# final_design.net
KiCad netlist of a schematic drawn in Altium Designer
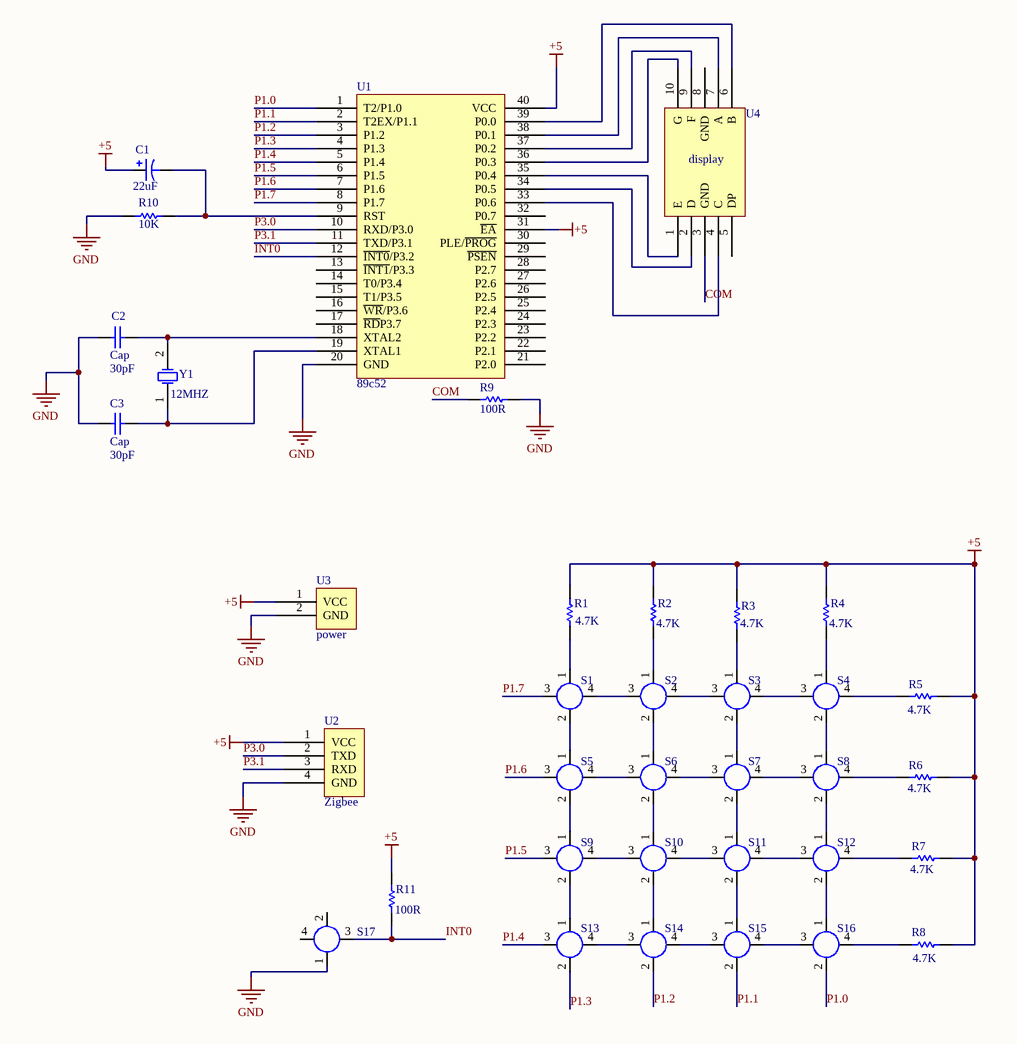
[diagram p0: final_design.SchDoc]

(export (version "E")
  (design (tool "Eeschema 10.0.6"))
  (components
    (comp (ref "C1")
      (value "22uF")
      (footprint "RB")
      (description "Polarized Capacitor (Radial)")
      (fields (field (name "Comment") "Cap Pol1") (field (name "PUBLISHER") "Altium Limited"))
      (libsource (lib "Miscellaneous Devices") (part "Cap Pol1"))
    )
    (comp (ref "C2")
      (value "Cap")
      (footprint "MLCC")
      (description "Capacitor")
      (fields (field (name "ALTIUM_VALUE") "30pF") (field (name "PUBLISHER") "Altium Limited"))
      (libsource (lib "Miscellaneous Devices") (part "Cap"))
    )
    (comp (ref "C3")
      (value "Cap")
      (footprint "MLCC")
      (description "Capacitor")
      (fields (field (name "ALTIUM_VALUE") "30pF") (field (name "PUBLISHER") "Altium Limited"))
      (libsource (lib "Miscellaneous Devices") (part "Cap"))
    )
    (comp (ref "R1")
      (value "4.7K")
      (footprint "Ris")
      (description "Resistor")
      (fields (field (name "Comment") "Res1") (field (name "PUBLISHER") "Altium Limited"))
      (libsource (lib "Miscellaneous Devices") (part "Res1"))
    )
    (comp (ref "R2")
      (value "4.7K")
      (footprint "Ris")
      (description "Resistor")
      (fields (field (name "Comment") "Res1") (field (name "PUBLISHER") "Altium Limited"))
      (libsource (lib "Miscellaneous Devices") (part "Res1"))
    )
    (comp (ref "R3")
      (value "4.7K")
      (footprint "Ris")
      (description "Resistor")
      (fields (field (name "Comment") "Res1") (field (name "PUBLISHER") "Altium Limited"))
      (libsource (lib "Miscellaneous Devices") (part "Res1"))
    )
    (comp (ref "R4")
      (value "4.7K")
      (footprint "Ris")
      (description "Resistor")
      (fields (field (name "Comment") "Res1") (field (name "PUBLISHER") "Altium Limited"))
      (libsource (lib "Miscellaneous Devices") (part "Res1"))
    )
    (comp (ref "R5")
      (value "4.7K")
      (footprint "Ris")
      (description "Resistor")
      (fields (field (name "Comment") "Res1") (field (name "PUBLISHER") "Altium Limited"))
      (libsource (lib "Miscellaneous Devices") (part "Res1"))
    )
    (comp (ref "R6")
      (value "4.7K")
      (footprint "Ris")
      (description "Resistor")
      (fields (field (name "Comment") "Res1") (field (name "PUBLISHER") "Altium Limited"))
      (libsource (lib "Miscellaneous Devices") (part "Res1"))
    )
    (comp (ref "R7")
      (value "4.7K")
      (footprint "Ris")
      (description "Resistor")
      (fields (field (name "Comment") "Res1") (field (name "PUBLISHER") "Altium Limited"))
      (libsource (lib "Miscellaneous Devices") (part "Res1"))
    )
    (comp (ref "R8")
      (value "4.7K")
      (footprint "Ris")
      (description "Resistor")
      (fields (field (name "Comment") "Res1") (field (name "PUBLISHER") "Altium Limited"))
      (libsource (lib "Miscellaneous Devices") (part "Res1"))
    )
    (comp (ref "R9")
      (value "100R")
      (footprint "Ris")
      (description "Resistor")
      (fields (field (name "Comment") "Res1") (field (name "PUBLISHER") "Altium Limited"))
      (libsource (lib "Miscellaneous Devices") (part "Res1"))
    )
    (comp (ref "R10")
      (value "10K")
      (footprint "Ris")
      (description "Resistor")
      (fields (field (name "Comment") "Res1") (field (name "PUBLISHER") "Altium Limited"))
      (libsource (lib "Miscellaneous Devices") (part "Res1"))
    )
    (comp (ref "R11")
      (value "100R")
      (footprint "Ris")
      (description "Resistor")
      (fields (field (name "Comment") "Res1") (field (name "PUBLISHER") "Altium Limited"))
      (libsource (lib "Miscellaneous Devices") (part "Res1"))
    )
    (comp (ref "S1")
      (value "Button-4feet")
      (footprint "Button-4feet")
      (libsource (lib "final_design") (part "Button-4feet"))
    )
    (comp (ref "S2")
      (value "Button-4feet")
      (footprint "Button-4feet")
      (libsource (lib "final_design") (part "Button-4feet"))
    )
    (comp (ref "S3")
      (value "Button-4feet")
      (footprint "Button-4feet")
      (libsource (lib "final_design") (part "Button-4feet"))
    )
    (comp (ref "S4")
      (value "Button-4feet")
      (footprint "Button-4feet")
      (libsource (lib "final_design") (part "Button-4feet"))
    )
    (comp (ref "S5")
      (value "Button-4feet")
      (footprint "Button-4feet")
      (libsource (lib "final_design") (part "Button-4feet"))
    )
    (comp (ref "S6")
      (value "Button-4feet")
      (footprint "Button-4feet")
      (libsource (lib "final_design") (part "Button-4feet"))
    )
    (comp (ref "S7")
      (value "Button-4feet")
      (footprint "Button-4feet")
      (libsource (lib "final_design") (part "Button-4feet"))
    )
    (comp (ref "S8")
      (value "Button-4feet")
      (footprint "Button-4feet")
      (libsource (lib "final_design") (part "Button-4feet"))
    )
    (comp (ref "S9")
      (value "Button-4feet")
      (footprint "Button-4feet")
      (libsource (lib "final_design") (part "Button-4feet"))
    )
    (comp (ref "S10")
      (value "Button-4feet")
      (footprint "Button-4feet")
      (libsource (lib "final_design") (part "Button-4feet"))
    )
    (comp (ref "S11")
      (value "Button-4feet")
      (footprint "Button-4feet")
      (libsource (lib "final_design") (part "Button-4feet"))
    )
    (comp (ref "S12")
      (value "Button-4feet")
      (footprint "Button-4feet")
      (libsource (lib "final_design") (part "Button-4feet"))
    )
    (comp (ref "S13")
      (value "Button-4feet")
      (footprint "Button-4feet")
      (libsource (lib "final_design") (part "Button-4feet"))
    )
    (comp (ref "S14")
      (value "Button-4feet")
      (footprint "Button-4feet")
      (libsource (lib "final_design") (part "Button-4feet"))
    )
    (comp (ref "S15")
      (value "Button-4feet")
      (footprint "Button-4feet")
      (libsource (lib "final_design") (part "Button-4feet"))
    )
    (comp (ref "S16")
      (value "Button-4feet")
      (footprint "Button-4feet")
      (libsource (lib "final_design") (part "Button-4feet"))
    )
    (comp (ref "S17")
      (value "Button-4feet")
      (footprint "Button-4feet")
      (libsource (lib "final_design") (part "Button-4feet"))
    )
    (comp (ref "U1") (value "89c52") (footprint "89C52") (libsource (lib "final_design") (part "89c52")))
    (comp (ref "U2") (value "Zigbee") (footprint "Zigbee") (libsource (lib "final_design") (part "Zigbee")))
    (comp (ref "U3") (value "power") (footprint "Power") (libsource (lib "final_design") (part "power")))
    (comp (ref "U4") (value "display") (footprint "Dsplay") (libsource (lib "final_design") (part "display")))
    (comp (ref "Y1")
      (value "12MHZ")
      (footprint "Oscillator-11.0592MHZ")
      (description "Crystal Oscillator")
      (fields (field (name "PUBLISHER") "Altium Limited"))
      (libsource (lib "Miscellaneous Devices") (part "XTAL"))
    )
  )
  (nets
    (net (code "1") (name "+5") (class "Default")
      (node (ref "C1") (pin "1") (pinfunction "1_1") (pintype "passive"))
      (node (ref "R1") (pin "2") (pinfunction "2_2") (pintype "passive"))
      (node (ref "R11") (pin "2") (pinfunction "2_2") (pintype "passive"))
      (node (ref "R2") (pin "1") (pinfunction "1_1") (pintype "passive"))
      (node (ref "R3") (pin "2") (pinfunction "2_2") (pintype "passive"))
      (node (ref "R4") (pin "2") (pinfunction "2_2") (pintype "passive"))
      (node (ref "R5") (pin "1") (pinfunction "1_1") (pintype "passive"))
      (node (ref "R6") (pin "1") (pinfunction "1_1") (pintype "passive"))
      (node (ref "R7") (pin "1") (pinfunction "1_1") (pintype "passive"))
      (node (ref "R8") (pin "1") (pinfunction "1_1") (pintype "passive"))
      (node (ref "U1") (pin "31") (pinfunction "~{EA}_31") (pintype "passive"))
      (node (ref "U1") (pin "40") (pinfunction "VCC_40") (pintype "passive"))
      (node (ref "U2") (pin "1") (pinfunction "VCC_1") (pintype "passive"))
      (node (ref "U3") (pin "1") (pinfunction "VCC_1") (pintype "passive"))
    )
    (net (code "2") (name "/COM") (class "Default")
      (node (ref "R9") (pin "2") (pinfunction "2_2") (pintype "passive"))
      (node (ref "U4") (pin "3") (pinfunction "GND_3") (pintype "passive"))
    )
    (net (code "3") (name "/INT0") (class "Default")
      (node (ref "R11") (pin "1") (pinfunction "1_1") (pintype "passive"))
      (node (ref "S17") (pin "3") (pinfunction "3_3") (pintype "passive"))
      (node (ref "U1") (pin "12") (pinfunction "~{INT0}/P3.2_12") (pintype "passive"))
    )
    (net (code "4") (name "/P1.0") (class "Default")
      (node (ref "S16") (pin "2") (pinfunction "2_2") (pintype "passive"))
      (node (ref "U1") (pin "1") (pinfunction "T2/P1.0_1") (pintype "passive"))
    )
    (net (code "5") (name "/P1.1") (class "Default")
      (node (ref "S15") (pin "2") (pinfunction "2_2") (pintype "passive"))
      (node (ref "U1") (pin "2") (pinfunction "T2EX/P1.1_2") (pintype "passive"))
    )
    (net (code "6") (name "/P1.2") (class "Default")
      (node (ref "S14") (pin "2") (pinfunction "2_2") (pintype "passive"))
      (node (ref "U1") (pin "3") (pinfunction "P1.2_3") (pintype "passive"))
    )
    (net (code "7") (name "/P1.3") (class "Default")
      (node (ref "S13") (pin "2") (pinfunction "2_2") (pintype "passive"))
      (node (ref "U1") (pin "4") (pinfunction "P1.3_4") (pintype "passive"))
    )
    (net (code "8") (name "/P1.4") (class "Default")
      (node (ref "S13") (pin "3") (pinfunction "3_3") (pintype "passive"))
      (node (ref "U1") (pin "5") (pinfunction "P1.4_5") (pintype "passive"))
    )
    (net (code "9") (name "/P1.5") (class "Default")
      (node (ref "S9") (pin "3") (pinfunction "3_3") (pintype "passive"))
      (node (ref "U1") (pin "6") (pinfunction "P1.5_6") (pintype "passive"))
    )
    (net (code "10") (name "/P1.6") (class "Default")
      (node (ref "S5") (pin "3") (pinfunction "3_3") (pintype "passive"))
      (node (ref "U1") (pin "7") (pinfunction "P1.6_7") (pintype "passive"))
    )
    (net (code "11") (name "/P1.7") (class "Default")
      (node (ref "S1") (pin "3") (pinfunction "3_3") (pintype "passive"))
      (node (ref "U1") (pin "8") (pinfunction "P1.7_8") (pintype "passive"))
    )
    (net (code "12") (name "/P3.0") (class "Default")
      (node (ref "U1") (pin "10") (pinfunction "RXD/P3.0_10") (pintype "passive"))
      (node (ref "U2") (pin "2") (pinfunction "TXD_2") (pintype "passive"))
    )
    (net (code "13") (name "/P3.1") (class "Default")
      (node (ref "U1") (pin "11") (pinfunction "TXD/P3.1_11") (pintype "passive"))
      (node (ref "U2") (pin "3") (pinfunction "RXD_3") (pintype "passive"))
    )
    (net (code "14") (name "GND") (class "Default")
      (node (ref "C2") (pin "1") (pinfunction "1_1") (pintype "passive"))
      (node (ref "C3") (pin "1") (pinfunction "1_1") (pintype "passive"))
      (node (ref "R10") (pin "2") (pinfunction "2_2") (pintype "passive"))
      (node (ref "R9") (pin "1") (pinfunction "1_1") (pintype "passive"))
      (node (ref "S17") (pin "1") (pinfunction "41_1") (pintype "passive"))
      (node (ref "U1") (pin "20") (pinfunction "GND_20") (pintype "passive"))
      (node (ref "U2") (pin "4") (pinfunction "GND_4") (pintype "passive"))
      (node (ref "U3") (pin "2") (pinfunction "GND_2") (pintype "passive"))
    )
    (net (code "15") (name "Net-(R5-Pad2)") (class "Default")
      (node (ref "R5") (pin "2") (pinfunction "2_2") (pintype "passive"))
      (node (ref "S4") (pin "4") (pinfunction "4_4") (pintype "passive"))
    )
    (net (code "16") (name "Net-(R6-Pad2)") (class "Default")
      (node (ref "R6") (pin "2") (pinfunction "2_2") (pintype "passive"))
      (node (ref "S8") (pin "4") (pinfunction "4_4") (pintype "passive"))
    )
    (net (code "17") (name "Net-(R7-Pad2)") (class "Default")
      (node (ref "R7") (pin "2") (pinfunction "2_2") (pintype "passive"))
      (node (ref "S12") (pin "4") (pinfunction "4_4") (pintype "passive"))
    )
    (net (code "18") (name "Net-(R8-Pad2)") (class "Default")
      (node (ref "R8") (pin "2") (pinfunction "2_2") (pintype "passive"))
      (node (ref "S16") (pin "4") (pinfunction "4_4") (pintype "passive"))
    )
    (net (code "19") (name "Net-(S1-41)") (class "Default")
      (node (ref "R1") (pin "1") (pinfunction "1_1") (pintype "passive"))
      (node (ref "S1") (pin "1") (pinfunction "41_1") (pintype "passive"))
    )
    (net (code "20") (name "Net-(S1-Pad4)") (class "Default")
      (node (ref "S1") (pin "4") (pinfunction "4_4") (pintype "passive"))
      (node (ref "S2") (pin "3") (pinfunction "3_3") (pintype "passive"))
    )
    (net (code "21") (name "Net-(S2-41)") (class "Default")
      (node (ref "R2") (pin "2") (pinfunction "2_2") (pintype "passive"))
      (node (ref "S2") (pin "1") (pinfunction "41_1") (pintype "passive"))
    )
    (net (code "22") (name "Net-(S2-Pad4)") (class "Default")
      (node (ref "S2") (pin "4") (pinfunction "4_4") (pintype "passive"))
      (node (ref "S3") (pin "3") (pinfunction "3_3") (pintype "passive"))
    )
    (net (code "23") (name "Net-(S3-41)") (class "Default")
      (node (ref "R3") (pin "1") (pinfunction "1_1") (pintype "passive"))
      (node (ref "S3") (pin "1") (pinfunction "41_1") (pintype "passive"))
    )
    (net (code "24") (name "Net-(S3-Pad4)") (class "Default")
      (node (ref "S3") (pin "4") (pinfunction "4_4") (pintype "passive"))
      (node (ref "S4") (pin "3") (pinfunction "3_3") (pintype "passive"))
    )
    (net (code "25") (name "Net-(S4-41)") (class "Default")
      (node (ref "R4") (pin "1") (pinfunction "1_1") (pintype "passive"))
      (node (ref "S4") (pin "1") (pinfunction "41_1") (pintype "passive"))
    )
    (net (code "26") (name "Net-(S5-41)") (class "Default")
      (node (ref "S1") (pin "2") (pinfunction "2_2") (pintype "passive"))
      (node (ref "S5") (pin "1") (pinfunction "41_1") (pintype "passive"))
    )
    (net (code "27") (name "Net-(S5-Pad4)") (class "Default")
      (node (ref "S5") (pin "4") (pinfunction "4_4") (pintype "passive"))
      (node (ref "S6") (pin "3") (pinfunction "3_3") (pintype "passive"))
    )
    (net (code "28") (name "Net-(S6-41)") (class "Default")
      (node (ref "S2") (pin "2") (pinfunction "2_2") (pintype "passive"))
      (node (ref "S6") (pin "1") (pinfunction "41_1") (pintype "passive"))
    )
    (net (code "29") (name "Net-(S6-Pad4)") (class "Default")
      (node (ref "S6") (pin "4") (pinfunction "4_4") (pintype "passive"))
      (node (ref "S7") (pin "3") (pinfunction "3_3") (pintype "passive"))
    )
    (net (code "30") (name "Net-(S7-41)") (class "Default")
      (node (ref "S3") (pin "2") (pinfunction "2_2") (pintype "passive"))
      (node (ref "S7") (pin "1") (pinfunction "41_1") (pintype "passive"))
    )
    (net (code "31") (name "Net-(S7-Pad4)") (class "Default")
      (node (ref "S7") (pin "4") (pinfunction "4_4") (pintype "passive"))
      (node (ref "S8") (pin "3") (pinfunction "3_3") (pintype "passive"))
    )
    (net (code "32") (name "Net-(S8-41)") (class "Default")
      (node (ref "S4") (pin "2") (pinfunction "2_2") (pintype "passive"))
      (node (ref "S8") (pin "1") (pinfunction "41_1") (pintype "passive"))
    )
    (net (code "33") (name "Net-(S9-41)") (class "Default")
      (node (ref "S5") (pin "2") (pinfunction "2_2") (pintype "passive"))
      (node (ref "S9") (pin "1") (pinfunction "41_1") (pintype "passive"))
    )
    (net (code "34") (name "Net-(S10-41)") (class "Default")
      (node (ref "S10") (pin "1") (pinfunction "41_1") (pintype "passive"))
      (node (ref "S6") (pin "2") (pinfunction "2_2") (pintype "passive"))
    )
    (net (code "35") (name "Net-(S10-Pad3)") (class "Default")
      (node (ref "S10") (pin "3") (pinfunction "3_3") (pintype "passive"))
      (node (ref "S9") (pin "4") (pinfunction "4_4") (pintype "passive"))
    )
    (net (code "36") (name "Net-(S10-Pad4)") (class "Default")
      (node (ref "S10") (pin "4") (pinfunction "4_4") (pintype "passive"))
      (node (ref "S11") (pin "3") (pinfunction "3_3") (pintype "passive"))
    )
    (net (code "37") (name "Net-(S11-41)") (class "Default")
      (node (ref "S11") (pin "1") (pinfunction "41_1") (pintype "passive"))
      (node (ref "S7") (pin "2") (pinfunction "2_2") (pintype "passive"))
    )
    (net (code "38") (name "Net-(S11-Pad4)") (class "Default")
      (node (ref "S11") (pin "4") (pinfunction "4_4") (pintype "passive"))
      (node (ref "S12") (pin "3") (pinfunction "3_3") (pintype "passive"))
    )
    (net (code "39") (name "Net-(S12-41)") (class "Default")
      (node (ref "S12") (pin "1") (pinfunction "41_1") (pintype "passive"))
      (node (ref "S8") (pin "2") (pinfunction "2_2") (pintype "passive"))
    )
    (net (code "40") (name "Net-(S13-41)") (class "Default")
      (node (ref "S13") (pin "1") (pinfunction "41_1") (pintype "passive"))
      (node (ref "S9") (pin "2") (pinfunction "2_2") (pintype "passive"))
    )
    (net (code "41") (name "Net-(S13-Pad4)") (class "Default")
      (node (ref "S13") (pin "4") (pinfunction "4_4") (pintype "passive"))
      (node (ref "S14") (pin "3") (pinfunction "3_3") (pintype "passive"))
    )
    (net (code "42") (name "Net-(S14-41)") (class "Default")
      (node (ref "S10") (pin "2") (pinfunction "2_2") (pintype "passive"))
      (node (ref "S14") (pin "1") (pinfunction "41_1") (pintype "passive"))
    )
    (net (code "43") (name "Net-(S14-Pad4)") (class "Default")
      (node (ref "S14") (pin "4") (pinfunction "4_4") (pintype "passive"))
      (node (ref "S15") (pin "3") (pinfunction "3_3") (pintype "passive"))
    )
    (net (code "44") (name "Net-(S15-41)") (class "Default")
      (node (ref "S11") (pin "2") (pinfunction "2_2") (pintype "passive"))
      (node (ref "S15") (pin "1") (pinfunction "41_1") (pintype "passive"))
    )
    (net (code "45") (name "Net-(S15-Pad4)") (class "Default")
      (node (ref "S15") (pin "4") (pinfunction "4_4") (pintype "passive"))
      (node (ref "S16") (pin "3") (pinfunction "3_3") (pintype "passive"))
    )
    (net (code "46") (name "Net-(S16-41)") (class "Default")
      (node (ref "S12") (pin "2") (pinfunction "2_2") (pintype "passive"))
      (node (ref "S16") (pin "1") (pinfunction "41_1") (pintype "passive"))
    )
    (net (code "47") (name "Net-(U1-P0.0)") (class "Default")
      (node (ref "U1") (pin "39") (pinfunction "P0.0_39") (pintype "passive"))
      (node (ref "U4") (pin "6") (pinfunction "B_6") (pintype "passive"))
    )
    (net (code "48") (name "Net-(U1-P0.1)") (class "Default")
      (node (ref "U1") (pin "38") (pinfunction "P0.1_38") (pintype "passive"))
      (node (ref "U4") (pin "7") (pinfunction "A_7") (pintype "passive"))
    )
    (net (code "49") (name "Net-(U1-P0.2)") (class "Default")
      (node (ref "U1") (pin "37") (pinfunction "P0.2_37") (pintype "passive"))
      (node (ref "U4") (pin "9") (pinfunction "F_9") (pintype "passive"))
    )
    (net (code "50") (name "Net-(U1-P0.3)") (class "Default")
      (node (ref "U1") (pin "36") (pinfunction "P0.3_36") (pintype "passive"))
      (node (ref "U4") (pin "10") (pinfunction "G_10") (pintype "passive"))
    )
    (net (code "51") (name "Net-(U1-P0.4)") (class "Default")
      (node (ref "U1") (pin "35") (pinfunction "P0.4_35") (pintype "passive"))
      (node (ref "U4") (pin "1") (pinfunction "E_1") (pintype "passive"))
    )
    (net (code "52") (name "Net-(U1-P0.5)") (class "Default")
      (node (ref "U1") (pin "34") (pinfunction "P0.5_34") (pintype "passive"))
      (node (ref "U4") (pin "2") (pinfunction "D_2") (pintype "passive"))
    )
    (net (code "53") (name "Net-(U1-P0.6)") (class "Default")
      (node (ref "U1") (pin "33") (pinfunction "P0.6_33") (pintype "passive"))
      (node (ref "U4") (pin "4") (pinfunction "C_4") (pintype "passive"))
    )
    (net (code "54") (name "Net-(U1-RST)") (class "Default")
      (node (ref "C1") (pin "2") (pinfunction "2_2") (pintype "passive"))
      (node (ref "R10") (pin "1") (pinfunction "1_1") (pintype "passive"))
      (node (ref "U1") (pin "9") (pinfunction "RST_9") (pintype "passive"))
    )
    (net (code "55") (name "Net-(U1-XTAL1)") (class "Default")
      (node (ref "C3") (pin "2") (pinfunction "2_2") (pintype "passive"))
      (node (ref "U1") (pin "19") (pinfunction "XTAL1_19") (pintype "passive"))
      (node (ref "Y1") (pin "1") (pinfunction "OSC1_1") (pintype "passive"))
    )
    (net (code "56") (name "Net-(U1-XTAL2)") (class "Default")
      (node (ref "C2") (pin "2") (pinfunction "2_2") (pintype "passive"))
      (node (ref "U1") (pin "18") (pinfunction "XTAL2_18") (pintype "passive"))
      (node (ref "Y1") (pin "2") (pinfunction "OSC2_2") (pintype "passive"))
    )
    (net (code "57") (name "unconnected-(S17-Pad2)") (class "Default")
      (node (ref "S17") (pin "2") (pinfunction "2_2") (pintype "passive"))
    )
    (net (code "58") (name "unconnected-(S17-Pad4)") (class "Default")
      (node (ref "S17") (pin "4") (pinfunction "4_4") (pintype "passive"))
    )
    (net (code "59") (name "unconnected-(U1-P0.7-Pad32)") (class "Default")
      (node (ref "U1") (pin "32") (pinfunction "P0.7_32") (pintype "passive"))
    )
    (net (code "60") (name "unconnected-(U1-P2.0-Pad21)") (class "Default")
      (node (ref "U1") (pin "21") (pinfunction "P2.0_21") (pintype "passive"))
    )
    (net (code "61") (name "unconnected-(U1-P2.1-Pad22)") (class "Default")
      (node (ref "U1") (pin "22") (pinfunction "P2.1_22") (pintype "passive"))
    )
    (net (code "62") (name "unconnected-(U1-P2.2-Pad23)") (class "Default")
      (node (ref "U1") (pin "23") (pinfunction "P2.2_23") (pintype "passive"))
    )
    (net (code "63") (name "unconnected-(U1-P2.3-Pad24)") (class "Default")
      (node (ref "U1") (pin "24") (pinfunction "P2.3_24") (pintype "passive"))
    )
    (net (code "64") (name "unconnected-(U1-P2.4-Pad25)") (class "Default")
      (node (ref "U1") (pin "25") (pinfunction "P2.4_25") (pintype "passive"))
    )
    (net (code "65") (name "unconnected-(U1-P2.5-Pad26)") (class "Default")
      (node (ref "U1") (pin "26") (pinfunction "P2.5_26") (pintype "passive"))
    )
    (net (code "66") (name "unconnected-(U1-P2.6-Pad27)") (class "Default")
      (node (ref "U1") (pin "27") (pinfunction "P2.6_27") (pintype "passive"))
    )
    (net (code "67") (name "unconnected-(U1-P2.7-Pad28)") (class "Default")
      (node (ref "U1") (pin "28") (pinfunction "P2.7_28") (pintype "passive"))
    )
    (net (code "68") (name "unconnected-(U1-PLE{slash}~{PROG}-Pad30)") (class "Default")
      (node (ref "U1") (pin "30") (pinfunction "PLE/~{PROG}_30") (pintype "passive"))
    )
    (net (code "69") (name "unconnected-(U1-T0{slash}P3.4-Pad14)") (class "Default")
      (node (ref "U1") (pin "14") (pinfunction "T0/P3.4_14") (pintype "passive"))
    )
    (net (code "70") (name "unconnected-(U1-T1{slash}P3.5-Pad15)") (class "Default")
      (node (ref "U1") (pin "15") (pinfunction "T1/P3.5_15") (pintype "passive"))
    )
    (net (code "71") (name "unconnected-(U1-~{INT1}{slash}P3.3-Pad13)") (class "Default")
      (node (ref "U1") (pin "13") (pinfunction "~{INT1}/P3.3_13") (pintype "passive"))
    )
    (net (code "72") (name "unconnected-(U1-~{PSEN}-Pad29)") (class "Default")
      (node (ref "U1") (pin "29") (pinfunction "~{PSEN}_29") (pintype "passive"))
    )
    (net (code "73") (name "unconnected-(U1-~{RD}P3.7-Pad17)") (class "Default")
      (node (ref "U1") (pin "17") (pinfunction "~{RD}P3.7_17") (pintype "passive"))
    )
    (net (code "74") (name "unconnected-(U1-~{WR}{slash}P3.6-Pad16)") (class "Default")
      (node (ref "U1") (pin "16") (pinfunction "~{WR}/P3.6_16") (pintype "passive"))
    )
    (net (code "75") (name "unconnected-(U4-DP-Pad5)") (class "Default")
      (node (ref "U4") (pin "5") (pinfunction "DP_5") (pintype "passive"))
    )
    (net (code "76") (name "unconnected-(U4-GND-Pad8)") (class "Default")
      (node (ref "U4") (pin "8") (pinfunction "GND_8") (pintype "passive"))
    )
  )
)
